# pt2MX.net
KiCad netlist of a schematic drawn in EAGLE
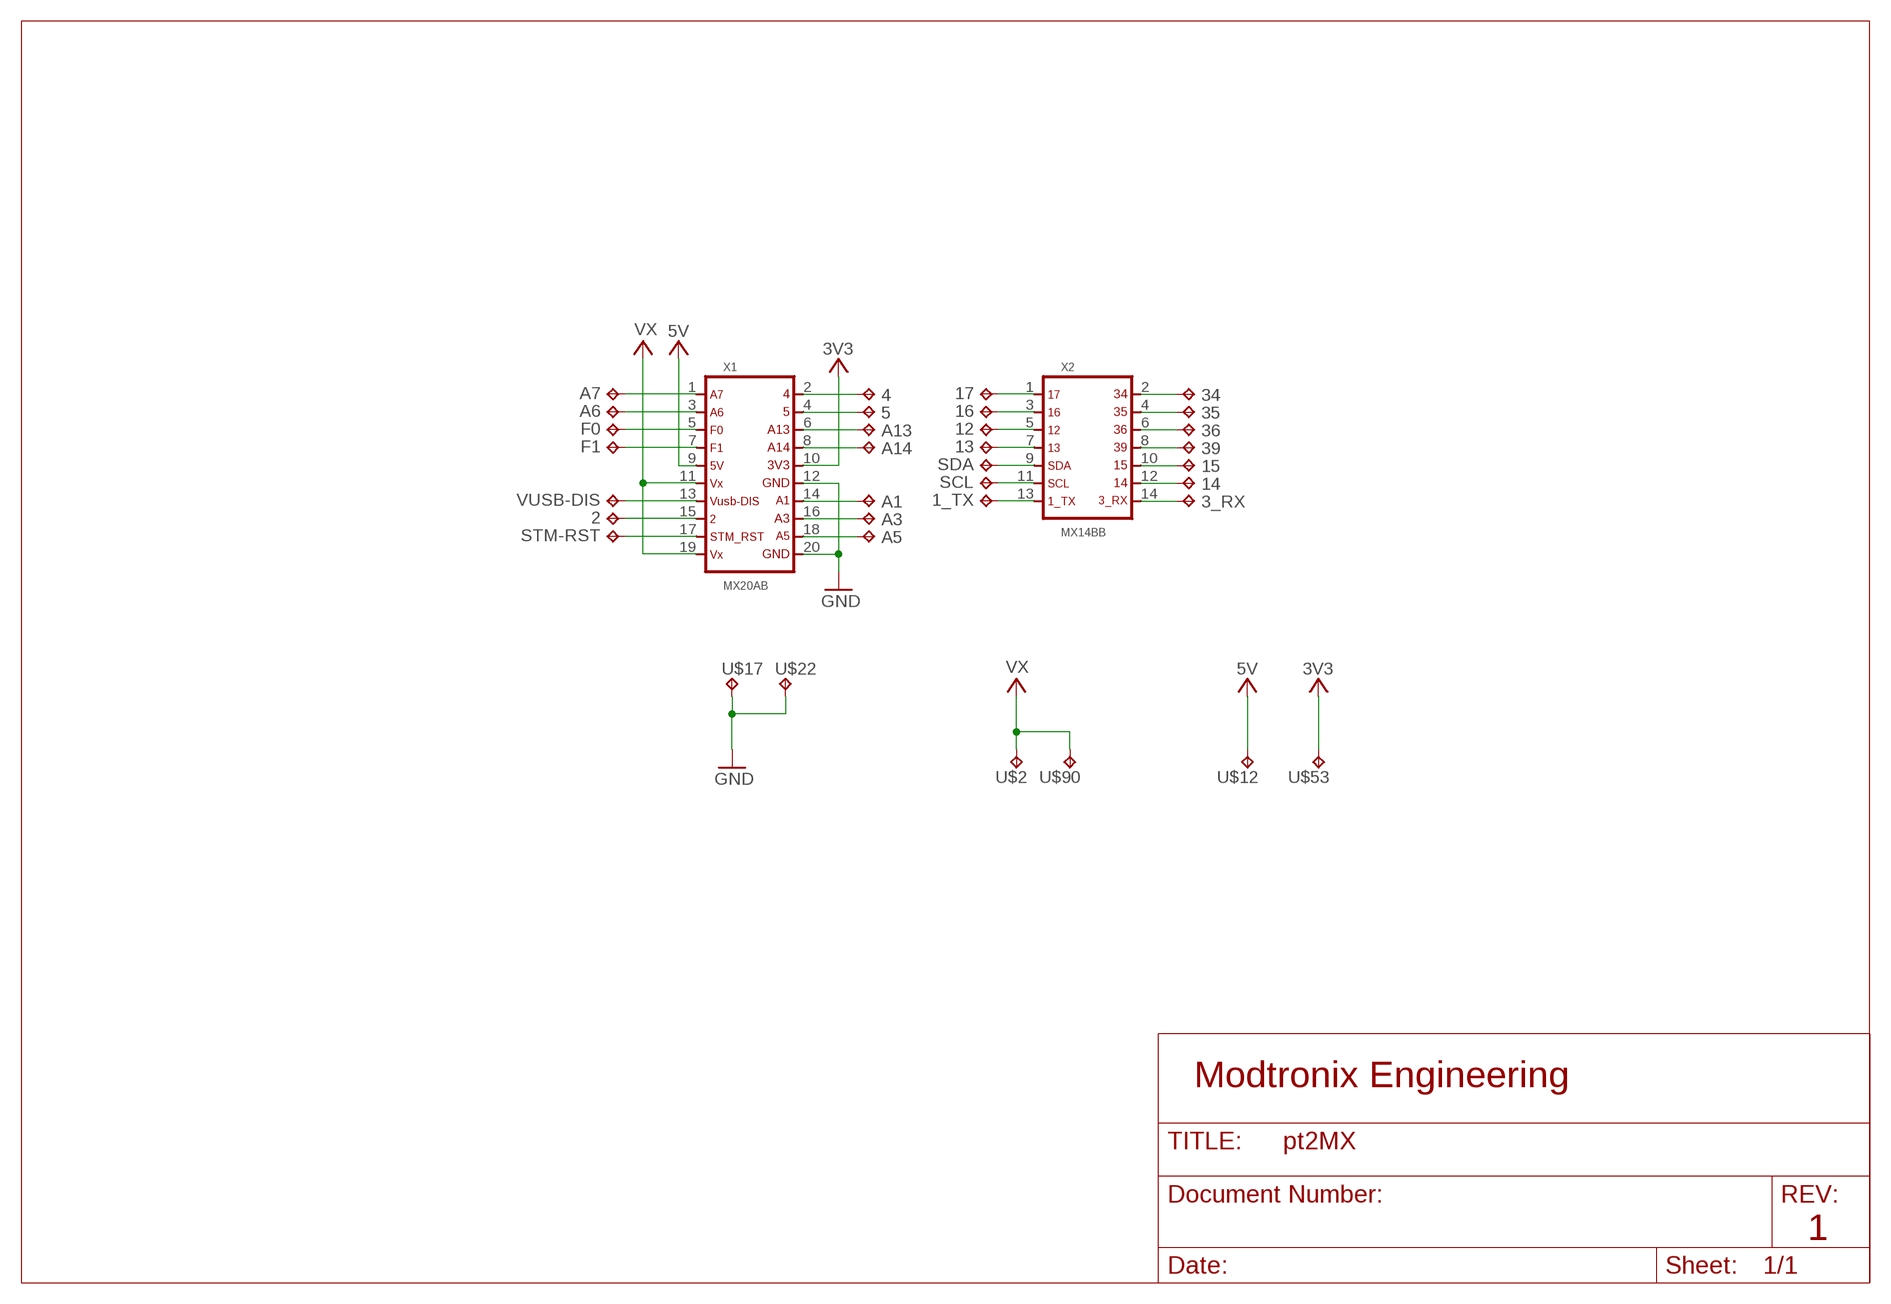
[diagram p0: schematic, sheet 1]

(export (version "E")
  (design (tool "Eeschema 10.0.6"))
  (components
    (comp (ref "1_TX")
      (value "TPD10-D200")
      (footprint "eagle-import:TP-10-D200")
      (libsource (lib "eagle-import") (part "TPD10-D200"))
    )
    (comp (ref "2")
      (value "TPD10-D200")
      (footprint "eagle-import:TP-10-D200")
      (libsource (lib "eagle-import") (part "TPD10-D200"))
    )
    (comp (ref "3_RX")
      (value "TPD10-D200")
      (footprint "eagle-import:TP-10-D200")
      (libsource (lib "eagle-import") (part "TPD10-D200"))
    )
    (comp (ref "4")
      (value "TPD10-D200")
      (footprint "eagle-import:TP-10-D200")
      (libsource (lib "eagle-import") (part "TPD10-D200"))
    )
    (comp (ref "5")
      (value "TPD10-D200")
      (footprint "eagle-import:TP-10-D200")
      (libsource (lib "eagle-import") (part "TPD10-D200"))
    )
    (comp (ref "12")
      (value "TPD10-D200")
      (footprint "eagle-import:TP-10-D200")
      (libsource (lib "eagle-import") (part "TPD10-D200"))
    )
    (comp (ref "13")
      (value "TPD10-D200")
      (footprint "eagle-import:TP-10-D200")
      (libsource (lib "eagle-import") (part "TPD10-D200"))
    )
    (comp (ref "14")
      (value "TPD10-D200")
      (footprint "eagle-import:TP-10-D200")
      (libsource (lib "eagle-import") (part "TPD10-D200"))
    )
    (comp (ref "15")
      (value "TPD10-D200")
      (footprint "eagle-import:TP-10-D200")
      (libsource (lib "eagle-import") (part "TPD10-D200"))
    )
    (comp (ref "16")
      (value "TPD10-D200")
      (footprint "eagle-import:TP-10-D200")
      (libsource (lib "eagle-import") (part "TPD10-D200"))
    )
    (comp (ref "17")
      (value "TPD10-D200")
      (footprint "eagle-import:TP-10-D200")
      (libsource (lib "eagle-import") (part "TPD10-D200"))
    )
    (comp (ref "34")
      (value "TPD10-D200")
      (footprint "eagle-import:TP-10-D200")
      (libsource (lib "eagle-import") (part "TPD10-D200"))
    )
    (comp (ref "35")
      (value "TPD10-D200")
      (footprint "eagle-import:TP-10-D200")
      (libsource (lib "eagle-import") (part "TPD10-D200"))
    )
    (comp (ref "36")
      (value "TPD10-D200")
      (footprint "eagle-import:TP-10-D200")
      (libsource (lib "eagle-import") (part "TPD10-D200"))
    )
    (comp (ref "39")
      (value "TPD10-D200")
      (footprint "eagle-import:TP-10-D200")
      (libsource (lib "eagle-import") (part "TPD10-D200"))
    )
    (comp (ref "A1")
      (value "TPD10-D200")
      (footprint "eagle-import:TP-10-D200")
      (libsource (lib "eagle-import") (part "TPD10-D200"))
    )
    (comp (ref "A3")
      (value "TPD10-D200")
      (footprint "eagle-import:TP-10-D200")
      (libsource (lib "eagle-import") (part "TPD10-D200"))
    )
    (comp (ref "A5")
      (value "TPD10-D200")
      (footprint "eagle-import:TP-10-D200")
      (libsource (lib "eagle-import") (part "TPD10-D200"))
    )
    (comp (ref "A6")
      (value "TPD10-D200")
      (footprint "eagle-import:TP-10-D200")
      (libsource (lib "eagle-import") (part "TPD10-D200"))
    )
    (comp (ref "A7")
      (value "TPD10-D200")
      (footprint "eagle-import:TP-10-D200")
      (libsource (lib "eagle-import") (part "TPD10-D200"))
    )
    (comp (ref "A13")
      (value "TPD10-D200")
      (footprint "eagle-import:TP-10-D200")
      (libsource (lib "eagle-import") (part "TPD10-D200"))
    )
    (comp (ref "A14")
      (value "TPD10-D200")
      (footprint "eagle-import:TP-10-D200")
      (libsource (lib "eagle-import") (part "TPD10-D200"))
    )
    (comp (ref "F0")
      (value "TPD10-D200")
      (footprint "eagle-import:TP-10-D200")
      (libsource (lib "eagle-import") (part "TPD10-D200"))
    )
    (comp (ref "F1")
      (value "TPD10-D200")
      (footprint "eagle-import:TP-10-D200")
      (libsource (lib "eagle-import") (part "TPD10-D200"))
    )
    (comp (ref "SCL")
      (value "TPD10-D200")
      (footprint "eagle-import:TP-10-D200")
      (libsource (lib "eagle-import") (part "TPD10-D200"))
    )
    (comp (ref "SDA")
      (value "TPD10-D200")
      (footprint "eagle-import:TP-10-D200")
      (libsource (lib "eagle-import") (part "TPD10-D200"))
    )
    (comp (ref "STM-RST")
      (value "TPD10-D200")
      (footprint "eagle-import:TP-10-D200")
      (libsource (lib "eagle-import") (part "TPD10-D200"))
    )
    (comp (ref "U$2")
      (value "TPD10-D200")
      (footprint "eagle-import:TP-10-D200")
      (libsource (lib "eagle-import") (part "TPD10-D200"))
    )
    (comp (ref "U$12")
      (value "TPD10-D200")
      (footprint "eagle-import:TP-10-D200")
      (libsource (lib "eagle-import") (part "TPD10-D200"))
    )
    (comp (ref "U$17")
      (value "TPD10-D200")
      (footprint "eagle-import:TP-10-D200")
      (libsource (lib "eagle-import") (part "TPD10-D200"))
    )
    (comp (ref "U$22")
      (value "TPD10-D200")
      (footprint "eagle-import:TP-10-D200")
      (libsource (lib "eagle-import") (part "TPD10-D200"))
    )
    (comp (ref "U$53")
      (value "TPD10-D200")
      (footprint "eagle-import:TP-10-D200")
      (libsource (lib "eagle-import") (part "TPD10-D200"))
    )
    (comp (ref "U$90")
      (value "TPD10-D200")
      (footprint "eagle-import:TP-10-D200")
      (libsource (lib "eagle-import") (part "TPD10-D200"))
    )
    (comp (ref "VUSB-DIS")
      (value "TPD10-D200")
      (footprint "eagle-import:TP-10-D200")
      (libsource (lib "eagle-import") (part "TPD10-D200"))
    )
    (comp (ref "X1")
      (value "MX20AB")
      (footprint "eagle-import:MA10-2-NONUM")
      (libsource (lib "eagle-import") (part "MX20AB"))
    )
    (comp (ref "X2")
      (value "MX14BB")
      (footprint "eagle-import:MA07-2-NONUM")
      (libsource (lib "eagle-import") (part "MX14BB"))
    )
  )
  (nets
    (net (code "1") (name "3V3") (class "Default")
      (node (ref "U$53") (pin "1") (pinfunction "TP_1") (pintype "input"))
      (node (ref "X1") (pin "10") (pinfunction "10_10") (pintype "passive"))
    )
    (net (code "2") (name "5V") (class "Default")
      (node (ref "U$12") (pin "1") (pinfunction "TP_1") (pintype "input"))
      (node (ref "X1") (pin "9") (pinfunction "9_9") (pintype "passive"))
    )
    (net (code "3") (name "GND") (class "Default")
      (node (ref "U$17") (pin "1") (pinfunction "TP_1") (pintype "input"))
      (node (ref "U$22") (pin "1") (pinfunction "TP_1") (pintype "input"))
      (node (ref "X1") (pin "12") (pinfunction "12_12") (pintype "passive"))
      (node (ref "X1") (pin "20") (pinfunction "20_20") (pintype "passive"))
    )
    (net (code "4") (name "Net-(1_TX-TP)") (class "Default")
      (node (ref "1_TX") (pin "1") (pinfunction "TP_1") (pintype "input"))
      (node (ref "X2") (pin "13") (pinfunction "13_13") (pintype "passive"))
    )
    (net (code "5") (name "Net-(2-TP)") (class "Default")
      (node (ref "2") (pin "1") (pinfunction "TP_1") (pintype "input"))
      (node (ref "X1") (pin "15") (pinfunction "15_15") (pintype "passive"))
    )
    (net (code "6") (name "Net-(3_RX-TP)") (class "Default")
      (node (ref "3_RX") (pin "1") (pinfunction "TP_1") (pintype "input"))
      (node (ref "X2") (pin "14") (pinfunction "14_14") (pintype "passive"))
    )
    (net (code "7") (name "Net-(4-TP)") (class "Default")
      (node (ref "4") (pin "1") (pinfunction "TP_1") (pintype "input"))
      (node (ref "X1") (pin "2") (pinfunction "2_2") (pintype "passive"))
    )
    (net (code "8") (name "Net-(5-TP)") (class "Default")
      (node (ref "5") (pin "1") (pinfunction "TP_1") (pintype "input"))
      (node (ref "X1") (pin "4") (pinfunction "4_4") (pintype "passive"))
    )
    (net (code "9") (name "Net-(12-TP)") (class "Default")
      (node (ref "12") (pin "1") (pinfunction "TP_1") (pintype "input"))
      (node (ref "X2") (pin "5") (pinfunction "5_5") (pintype "passive"))
    )
    (net (code "10") (name "Net-(13-TP)") (class "Default")
      (node (ref "13") (pin "1") (pinfunction "TP_1") (pintype "input"))
      (node (ref "X2") (pin "7") (pinfunction "7_7") (pintype "passive"))
    )
    (net (code "11") (name "Net-(14-TP)") (class "Default")
      (node (ref "14") (pin "1") (pinfunction "TP_1") (pintype "input"))
      (node (ref "X2") (pin "12") (pinfunction "12_12") (pintype "passive"))
    )
    (net (code "12") (name "Net-(15-TP)") (class "Default")
      (node (ref "15") (pin "1") (pinfunction "TP_1") (pintype "input"))
      (node (ref "X2") (pin "10") (pinfunction "10_10") (pintype "passive"))
    )
    (net (code "13") (name "Net-(16-TP)") (class "Default")
      (node (ref "16") (pin "1") (pinfunction "TP_1") (pintype "input"))
      (node (ref "X2") (pin "3") (pinfunction "3_3") (pintype "passive"))
    )
    (net (code "14") (name "Net-(17-TP)") (class "Default")
      (node (ref "17") (pin "1") (pinfunction "TP_1") (pintype "input"))
      (node (ref "X2") (pin "1") (pinfunction "1_1") (pintype "passive"))
    )
    (net (code "15") (name "Net-(34-TP)") (class "Default")
      (node (ref "34") (pin "1") (pinfunction "TP_1") (pintype "input"))
      (node (ref "X2") (pin "2") (pinfunction "2_2") (pintype "passive"))
    )
    (net (code "16") (name "Net-(35-TP)") (class "Default")
      (node (ref "35") (pin "1") (pinfunction "TP_1") (pintype "input"))
      (node (ref "X2") (pin "4") (pinfunction "4_4") (pintype "passive"))
    )
    (net (code "17") (name "Net-(36-TP)") (class "Default")
      (node (ref "36") (pin "1") (pinfunction "TP_1") (pintype "input"))
      (node (ref "X2") (pin "6") (pinfunction "6_6") (pintype "passive"))
    )
    (net (code "18") (name "Net-(39-TP)") (class "Default")
      (node (ref "39") (pin "1") (pinfunction "TP_1") (pintype "input"))
      (node (ref "X2") (pin "8") (pinfunction "8_8") (pintype "passive"))
    )
    (net (code "19") (name "Net-(A1-TP)") (class "Default")
      (node (ref "A1") (pin "1") (pinfunction "TP_1") (pintype "input"))
      (node (ref "X1") (pin "14") (pinfunction "14_14") (pintype "passive"))
    )
    (net (code "20") (name "Net-(A3-TP)") (class "Default")
      (node (ref "A3") (pin "1") (pinfunction "TP_1") (pintype "input"))
      (node (ref "X1") (pin "16") (pinfunction "16_16") (pintype "passive"))
    )
    (net (code "21") (name "Net-(A5-TP)") (class "Default")
      (node (ref "A5") (pin "1") (pinfunction "TP_1") (pintype "input"))
      (node (ref "X1") (pin "18") (pinfunction "18_18") (pintype "passive"))
    )
    (net (code "22") (name "Net-(A6-TP)") (class "Default")
      (node (ref "A6") (pin "1") (pinfunction "TP_1") (pintype "input"))
      (node (ref "X1") (pin "3") (pinfunction "3_3") (pintype "passive"))
    )
    (net (code "23") (name "Net-(A7-TP)") (class "Default")
      (node (ref "A7") (pin "1") (pinfunction "TP_1") (pintype "input"))
      (node (ref "X1") (pin "1") (pinfunction "1_1") (pintype "passive"))
    )
    (net (code "24") (name "Net-(A13-TP)") (class "Default")
      (node (ref "A13") (pin "1") (pinfunction "TP_1") (pintype "input"))
      (node (ref "X1") (pin "6") (pinfunction "6_6") (pintype "passive"))
    )
    (net (code "25") (name "Net-(A14-TP)") (class "Default")
      (node (ref "A14") (pin "1") (pinfunction "TP_1") (pintype "input"))
      (node (ref "X1") (pin "8") (pinfunction "8_8") (pintype "passive"))
    )
    (net (code "26") (name "Net-(F0-TP)") (class "Default")
      (node (ref "F0") (pin "1") (pinfunction "TP_1") (pintype "input"))
      (node (ref "X1") (pin "5") (pinfunction "5_5") (pintype "passive"))
    )
    (net (code "27") (name "Net-(F1-TP)") (class "Default")
      (node (ref "F1") (pin "1") (pinfunction "TP_1") (pintype "input"))
      (node (ref "X1") (pin "7") (pinfunction "7_7") (pintype "passive"))
    )
    (net (code "28") (name "Net-(SCL-TP)") (class "Default")
      (node (ref "SCL") (pin "1") (pinfunction "TP_1") (pintype "input"))
      (node (ref "X2") (pin "11") (pinfunction "11_11") (pintype "passive"))
    )
    (net (code "29") (name "Net-(SDA-TP)") (class "Default")
      (node (ref "SDA") (pin "1") (pinfunction "TP_1") (pintype "input"))
      (node (ref "X2") (pin "9") (pinfunction "9_9") (pintype "passive"))
    )
    (net (code "30") (name "Net-(STM-RST-TP)") (class "Default")
      (node (ref "STM-RST") (pin "1") (pinfunction "TP_1") (pintype "input"))
      (node (ref "X1") (pin "17") (pinfunction "17_17") (pintype "passive"))
    )
    (net (code "31") (name "Net-(VUSB-DIS-TP)") (class "Default")
      (node (ref "VUSB-DIS") (pin "1") (pinfunction "TP_1") (pintype "input"))
      (node (ref "X1") (pin "13") (pinfunction "13_13") (pintype "passive"))
    )
    (net (code "32") (name "VX") (class "Default")
      (node (ref "U$2") (pin "1") (pinfunction "TP_1") (pintype "input"))
      (node (ref "U$90") (pin "1") (pinfunction "TP_1") (pintype "input"))
      (node (ref "X1") (pin "11") (pinfunction "11_11") (pintype "passive"))
      (node (ref "X1") (pin "19") (pinfunction "19_19") (pintype "passive"))
    )
  )
)
